# Power.net
KiCad netlist of a schematic drawn in Altium Designer
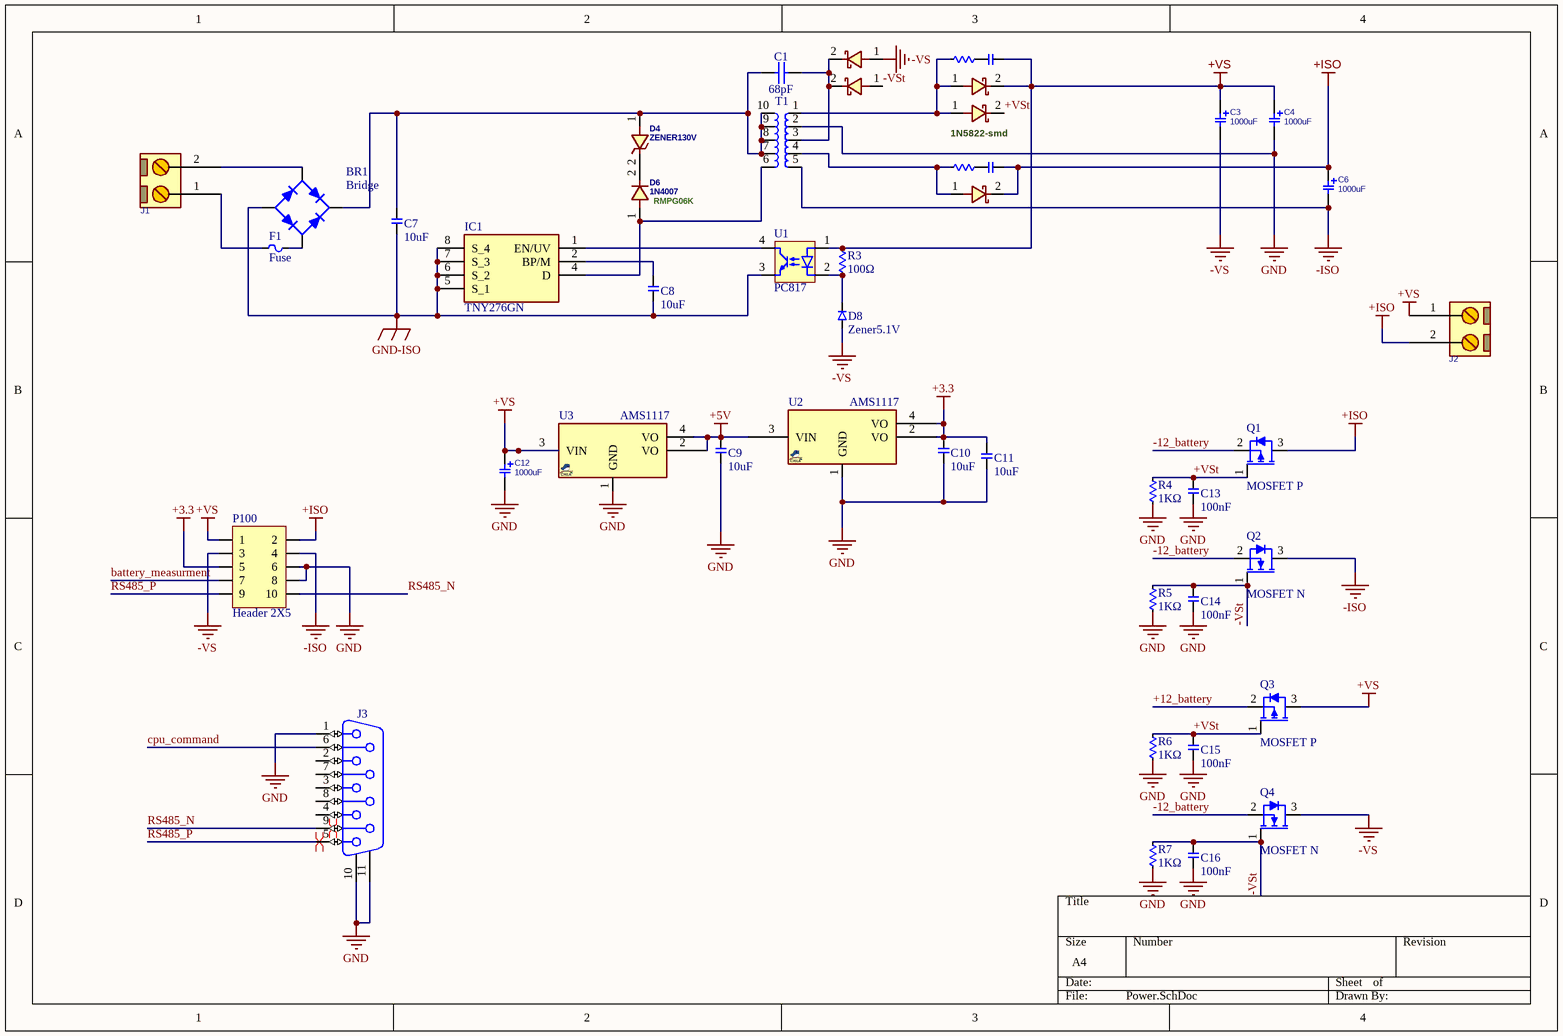
[diagram p0: Power.SchDoc]

(export (version "E")
  (design (tool "Eeschema 10.0.6"))
  (components
    (comp (ref "BR1")
      (value "Bridge")
      (footprint "SOP254P690X270-4L")
      (libsource (lib "Shahnahad") (part "Bridge"))
    )
    (comp (ref "C1")
      (value "68pF")
      (footprint "C_CER_D12")
      (description "Non-polarised capacitor")
      (fields
        (field (name "PART NUMBER") "CCR_68PF_760VAC_10%_VISHAY_VY1")
        (field (name "VOLTAGE") "760VAC")
        (field (name "AUTHOR") "CERN DEM JLC")
      )
      (libsource (lib "Capacitors") (part "Capacitor - non polarized"))
    )
    (comp (ref "C2")
      (value "560pF")
      (footprint "CAP 0603 560p")
      (libsource (lib "Shahnahad") (part "CAP 560pF"))
    )
    (comp (ref "C3")
      (value "1000uF")
      (footprint "C_EL_10X12")
      (description "CAP, THD, ELEC, 10uF, 25V")
      (fields (field (name "MANF") "MANF") (field (name "MANF_P#") "MANF_PART#"))
      (libsource (lib "CapElect_passive") (part "CAP_THD_EL_10u25V"))
    )
    (comp (ref "C4")
      (value "1000uF")
      (footprint "C_EL_10X12")
      (description "CAP, THD, ELEC, 10uF, 25V")
      (fields (field (name "MANF") "MANF") (field (name "MANF_P#") "MANF_PART#"))
      (libsource (lib "CapElect_passive") (part "CAP_THD_EL_10u25V"))
    )
    (comp (ref "C5")
      (value "560pF")
      (footprint "CAP 0603 560p")
      (libsource (lib "Shahnahad") (part "CAP 560pF"))
    )
    (comp (ref "C6")
      (value "1000uF")
      (footprint "C_EL_10X12")
      (description "CAP, THD, ELEC, 10uF, 25V")
      (fields (field (name "MANF") "MANF") (field (name "MANF_P#") "MANF_PART#"))
      (libsource (lib "CapElect_passive") (part "CAP_THD_EL_10u25V"))
    )
    (comp (ref "C7") (value "10uF") (footprint "C_EL_10X12") (libsource (lib "Shahnahad") (part "CAP 10uF")))
    (comp (ref "C8") (value "10uF") (footprint "C_CER_M5") (libsource (lib "Shahnahad") (part "CAP 10uF")))
    (comp (ref "C9")
      (value "10uF")
      (footprint "CAP 0805 10u")
      (libsource (lib "Shahnahad") (part "CAP 10uF"))
    )
    (comp (ref "C10")
      (value "10uF")
      (footprint "CAP 0805 10u")
      (libsource (lib "Shahnahad") (part "CAP 10uF"))
    )
    (comp (ref "C11")
      (value "10uF")
      (footprint "CAP 0805 10u")
      (libsource (lib "Shahnahad") (part "CAP 10uF"))
    )
    (comp (ref "C12")
      (value "1000uF")
      (footprint "C_EL_10X12")
      (description "CAP, THD, ELEC, 10uF, 25V")
      (fields (field (name "MANF") "MANF") (field (name "MANF_P#") "MANF_PART#"))
      (libsource (lib "CapElect_passive") (part "CAP_THD_EL_10u25V"))
    )
    (comp (ref "C13")
      (value "100nF")
      (footprint "CAP 0603 100n")
      (libsource (lib "Shahnahad") (part "CAP 100nF"))
    )
    (comp (ref "C14")
      (value "100nF")
      (footprint "CAP 0603 100n")
      (libsource (lib "Shahnahad") (part "CAP 100nF"))
    )
    (comp (ref "C15")
      (value "100nF")
      (footprint "CAP 0603 100n")
      (libsource (lib "Shahnahad") (part "CAP 100nF"))
    )
    (comp (ref "C16")
      (value "100nF")
      (footprint "CAP 0603 100n")
      (libsource (lib "Shahnahad") (part "CAP 100nF"))
    )
    (comp (ref "D1")
      (value "SS34")
      (footprint "D_SMB")
      (description "DIODE, SCHOTTKY, 20V, 3A")
      (fields (field (name "MANF") "VISHAY"))
      (libsource (lib "diode") (part "DIODE_SMD_SCHOTTKY_SS34"))
    )
    (comp (ref "D2")
      (value "SS34")
      (footprint "d_sod123w")
      (description "DIODE, SCHOTTKY, 20V, 3A")
      (fields (field (name "MANF") "VISHAY"))
      (libsource (lib "diode") (part "DIODE_SMD_SCHOTTKY_SS34"))
    )
    (comp (ref "D3")
      (value "SS34")
      (footprint "D_SMB")
      (description "DIODE, SCHOTTKY, 20V, 3A")
      (fields (field (name "MANF") "VISHAY"))
      (libsource (lib "diode") (part "DIODE_SMD_SCHOTTKY_SS34"))
    )
    (comp (ref "D4")
      (value "ZENER130V")
      (footprint "D_SMB")
      (description "DIODE, ZENER, 1W")
      (fields (field (name "MANF") "Diodes") (field (name "MANF_P#") "ZENER15V"))
      (libsource (lib "diode") (part "DIODE_THD_ZENER_1W"))
    )
    (comp (ref "D5")
      (value "SS34")
      (footprint "D_SOD123W")
      (description "DIODE, SCHOTTKY, 20V, 3A")
      (fields (field (name "MANF") "VISHAY"))
      (libsource (lib "diode") (part "DIODE_SMD_SCHOTTKY_SS34"))
    )
    (comp (ref "D6")
      (value "1N4007")
      (footprint "D_SMB")
      (description "DIODE, GENERAL PURPOSE, 1000V/1A")
      (fields (field (name "MANF") "Diodes"))
      (libsource (lib "diode") (part "DIODE_THD_1N4007"))
    )
    (comp (ref "D7")
      (value "SS34")
      (footprint "D_SMB")
      (description "DIODE, SCHOTTKY, 20V, 3A")
      (fields (field (name "MANF") "VISHAY"))
      (libsource (lib "diode") (part "DIODE_SMD_SCHOTTKY_SS34"))
    )
    (comp (ref "D8")
      (value "Zener5.1V")
      (footprint "DIOMELF3515L")
      (libsource (lib "Shahnahad") (part "Diode"))
    )
    (comp (ref "F1") (value "Fuse") (footprint "Fuse 2410") (libsource (lib "Shahnahad") (part "Fuse")))
    (comp (ref "IC1")
      (value "TNY276GN")
      (footprint "SMD-8C")
      (description "Integrated Circuit")
      (fields (field (name "MOUSER PART NUMBER") "869-TNY276GN") (field (name "RS PART NUMBER") "0533737"))
      (libsource (lib "SamacSys") (part "TNY276GN"))
    )
    (comp (ref "J1")
      (value "CONN_TB2")
      (footprint "TBG_2")
      (description "CONN, TERMINAL BLOCK, 5.08mm pitch")
      (libsource (lib "") (part "CONN_TB2_1"))
    )
    (comp (ref "J2")
      (value "CONN_TB2")
      (footprint "TBG_2")
      (description "CONN, TERMINAL BLOCK, 5.08mm pitch")
      (libsource (lib "Chila") (part "CONN_TB2"))
    )
    (comp (ref "J3")
      (value "D-Sub 9F")
      (footprint "FCI_D09S24A4GV00LF")
      (description "Connector D-sub 9 Female")
      (fields
        (field (name "PART NUMBER") "FCI_D09S24A4GV00LF")
        (field (name "MANUFACTURER") "FCI")
        (field (name "AUTHOR") "CERN DEM JMW")
      )
      (libsource (lib "Connectors") (part "Connector D-sub 9 Female"))
    )
    (comp (ref "P100")
      (value "Header 2X5")
      (footprint "HDR 2X5 F ST 2.54")
      (libsource (lib "Shahnahad") (part "Header 2X5"))
    )
    (comp (ref "Q1") (value "MOSFET P") (footprint "SOT23") (libsource (lib "Shahnahad") (part "MOSFET P")))
    (comp (ref "Q2") (value "MOSFET N") (footprint "SOT23") (libsource (lib "Shahnahad") (part "MOSFET N")))
    (comp (ref "Q3") (value "MOSFET P") (footprint "SOT23") (libsource (lib "Shahnahad") (part "MOSFET P")))
    (comp (ref "Q4") (value "MOSFET N") (footprint "SOT23") (libsource (lib "Shahnahad") (part "MOSFET N")))
    (comp (ref "R1") (value "18Ω") (footprint "RES 0603 18") (libsource (lib "Shahnahad") (part "RES 18")))
    (comp (ref "R2") (value "18Ω") (footprint "RES 0603 18") (libsource (lib "Shahnahad") (part "RES 18")))
    (comp (ref "R3") (value "100Ω") (footprint "RES 0603 100") (libsource (lib "Shahnahad") (part "RES 100")))
    (comp (ref "R4") (value "1KΩ") (footprint "RES 0603 1K") (libsource (lib "Shahnahad") (part "RES 1K")))
    (comp (ref "R5") (value "1KΩ") (footprint "RES 0603 1K") (libsource (lib "Shahnahad") (part "RES 1K")))
    (comp (ref "R6") (value "1KΩ") (footprint "RES 0603 1K") (libsource (lib "Shahnahad") (part "RES 1K")))
    (comp (ref "R7") (value "1KΩ") (footprint "RES 0603 1K") (libsource (lib "Shahnahad") (part "RES 1K")))
    (comp (ref "T1")
      (value "Transformer 5+5")
      (footprint "EE19 5+5")
      (libsource (lib "Shahnahad") (part "Transformer 5+5"))
    )
    (comp (ref "U1") (value "PC817") (footprint "PC817") (libsource (lib "Shahnahad") (part "PC817")))
    (comp (ref "U2")
      (value "AMS1117")
      (footprint "SOT223_4")
      (description "REG, Linear, LDO1V, 0.8A, SOT-223")
      (fields
        (field (name "MANF_P#") "LD1117, LM1117, AMS1117, TLV1117, REG1117, NCP1117, LT1117, SPX1117")
        (field (name "MANF") "TI, ON, ST")
      )
      (libsource (lib "reg_linear_1117") (part "VREG_1117_SOT223"))
    )
    (comp (ref "U3")
      (value "AMS1117")
      (footprint "SOT223_4")
      (description "REG, Linear, LDO1V, 0.8A, SOT-223")
      (fields
        (field (name "MANF_P#") "LD1117, LM1117, AMS1117, TLV1117, REG1117, NCP1117, LT1117, SPX1117")
        (field (name "MANF") "TI, ON, ST")
      )
      (libsource (lib "reg_linear_1117") (part "VREG_1117_SOT223"))
    )
  )
  (nets
    (net (code "1") (name "+3.3") (class "Default")
      (node (ref "C10") (pin "1") (pintype "passive"))
      (node (ref "C11") (pin "1") (pintype "passive"))
      (node (ref "P100") (pin "5") (pinfunction "5_5") (pintype "passive"))
      (node (ref "U2") (pin "2") (pinfunction "VO_2") (pintype "passive"))
      (node (ref "U2") (pin "4") (pinfunction "VO_4") (pintype "passive"))
    )
    (net (code "2") (name "+5V") (class "Default")
      (node (ref "C9") (pin "1") (pintype "passive"))
      (node (ref "U2") (pin "3") (pinfunction "VIN_3") (pintype "passive"))
      (node (ref "U3") (pin "2") (pinfunction "VO_2") (pintype "passive"))
      (node (ref "U3") (pin "4") (pinfunction "VO_4") (pintype "passive"))
    )
    (net (code "3") (name "+ISO") (class "Default")
      (node (ref "C5") (pin "2") (pintype "passive"))
      (node (ref "C6") (pin "1") (pinfunction "1_1") (pintype "passive"))
      (node (ref "D7") (pin "2") (pinfunction "2_2") (pintype "passive"))
      (node (ref "J2") (pin "2") (pinfunction "2_2") (pintype "passive"))
      (node (ref "P100") (pin "2") (pinfunction "2_2") (pintype "passive"))
      (node (ref "Q1") (pin "3") (pinfunction "D_3") (pintype "passive"))
    )
    (net (code "4") (name "+VS") (class "Default")
      (node (ref "C12") (pin "1") (pinfunction "1_1") (pintype "passive"))
      (node (ref "C2") (pin "2") (pintype "passive"))
      (node (ref "C3") (pin "1") (pinfunction "1_1") (pintype "passive"))
      (node (ref "C4") (pin "1") (pinfunction "1_1") (pintype "passive"))
      (node (ref "D3") (pin "2") (pinfunction "2_2") (pintype "passive"))
      (node (ref "J2") (pin "1") (pinfunction "1_1") (pintype "passive"))
      (node (ref "P100") (pin "1") (pinfunction "1_1") (pintype "passive"))
      (node (ref "Q3") (pin "3") (pinfunction "D_3") (pintype "passive"))
      (node (ref "R3") (pin "2") (pintype "passive"))
      (node (ref "U1") (pin "1") (pinfunction "1_1") (pintype "passive"))
      (node (ref "U3") (pin "3") (pinfunction "VIN_3") (pintype "passive"))
    )
    (net (code "5") (name "-ISO") (class "Default")
      (node (ref "C6") (pin "2") (pinfunction "2_2") (pintype "passive"))
      (node (ref "P100") (pin "4") (pinfunction "4_4") (pintype "passive"))
      (node (ref "Q2") (pin "3") (pinfunction "D_3") (pintype "passive"))
      (node (ref "T1") (pin "5") (pintype "passive"))
    )
    (net (code "6") (name "-VS") (class "Default")
      (node (ref "C3") (pin "2") (pinfunction "2_2") (pintype "passive"))
      (node (ref "D1") (pin "1") (pinfunction "1_1") (pintype "passive"))
      (node (ref "D8") (pin "2") (pintype "passive"))
      (node (ref "P100") (pin "3") (pinfunction "3_3") (pintype "passive"))
      (node (ref "Q4") (pin "3") (pinfunction "D_3") (pintype "passive"))
    )
    (net (code "7") (name "/+12_battery") (class "Default")
      (node (ref "Q3") (pin "2") (pinfunction "S_2") (pintype "passive"))
    )
    (net (code "8") (name "/+VSt") (class "Default")
      (node (ref "C13") (pin "1") (pintype "passive"))
      (node (ref "C15") (pin "1") (pintype "passive"))
      (node (ref "D5") (pin "2") (pinfunction "2_2") (pintype "passive"))
      (node (ref "Q1") (pin "1") (pinfunction "G_1") (pintype "passive"))
      (node (ref "Q3") (pin "1") (pinfunction "G_1") (pintype "passive"))
      (node (ref "R4") (pin "1") (pintype "passive"))
      (node (ref "R6") (pin "1") (pintype "passive"))
    )
    (net (code "9") (name "/-12_battery") (class "Default")
      (node (ref "Q1") (pin "2") (pinfunction "S_2") (pintype "passive"))
      (node (ref "Q2") (pin "2") (pinfunction "S_2") (pintype "passive"))
      (node (ref "Q4") (pin "2") (pinfunction "S_2") (pintype "passive"))
    )
    (net (code "10") (name "/-VSt") (class "Default")
      (node (ref "C14") (pin "1") (pintype "passive"))
      (node (ref "C16") (pin "1") (pintype "passive"))
      (node (ref "D2") (pin "1") (pinfunction "1_1") (pintype "passive"))
      (node (ref "Q2") (pin "1") (pinfunction "G_1") (pintype "passive"))
      (node (ref "Q4") (pin "1") (pinfunction "G_1") (pintype "passive"))
      (node (ref "R5") (pin "1") (pintype "passive"))
      (node (ref "R7") (pin "1") (pintype "passive"))
    )
    (net (code "11") (name "/RS485_N") (class "Default")
      (node (ref "J3") (pin "9") (pinfunction "9_9") (pintype "bidirectional"))
      (node (ref "P100") (pin "10") (pinfunction "10_10") (pintype "passive"))
    )
    (net (code "12") (name "/RS485_P") (class "Default")
      (node (ref "J3") (pin "5") (pinfunction "5_5") (pintype "bidirectional"))
      (node (ref "P100") (pin "9") (pinfunction "9_9") (pintype "passive"))
    )
    (net (code "13") (name "/battery_measurment") (class "Default")
      (node (ref "P100") (pin "7") (pinfunction "7_7") (pintype "passive"))
    )
    (net (code "14") (name "/cpu_command") (class "Default")
      (node (ref "J3") (pin "6") (pinfunction "6_6") (pintype "bidirectional"))
    )
    (net (code "15") (name "GND") (class "Default")
      (node (ref "C10") (pin "2") (pintype "passive"))
      (node (ref "C11") (pin "2") (pintype "passive"))
      (node (ref "C12") (pin "2") (pinfunction "2_2") (pintype "passive"))
      (node (ref "C13") (pin "2") (pintype "passive"))
      (node (ref "C14") (pin "2") (pintype "passive"))
      (node (ref "C15") (pin "2") (pintype "passive"))
      (node (ref "C16") (pin "2") (pintype "passive"))
      (node (ref "C4") (pin "2") (pinfunction "2_2") (pintype "passive"))
      (node (ref "C9") (pin "2") (pintype "passive"))
      (node (ref "J3") (pin "1") (pinfunction "1_1") (pintype "bidirectional"))
      (node (ref "J3") (pin "10") (pinfunction "10_10") (pintype "passive"))
      (node (ref "J3") (pin "11") (pinfunction "11_11") (pintype "passive"))
      (node (ref "P100") (pin "6") (pinfunction "6_6") (pintype "passive"))
      (node (ref "P100") (pin "8") (pinfunction "8_8") (pintype "passive"))
      (node (ref "R4") (pin "2") (pintype "passive"))
      (node (ref "R5") (pin "2") (pintype "passive"))
      (node (ref "R6") (pin "2") (pintype "passive"))
      (node (ref "R7") (pin "2") (pintype "passive"))
      (node (ref "T1") (pin "2") (pintype "passive"))
      (node (ref "U2") (pin "1") (pinfunction "GND_1") (pintype "passive"))
      (node (ref "U3") (pin "1") (pinfunction "GND_1") (pintype "passive"))
    )
    (net (code "16") (name "GND-ISO") (class "Default")
      (node (ref "BR1") (pin "2") (pinfunction "-_2") (pintype "passive"))
      (node (ref "C7") (pin "2") (pintype "passive"))
      (node (ref "C8") (pin "2") (pintype "passive"))
      (node (ref "IC1") (pin "5") (pinfunction "S_1_5") (pintype "passive"))
      (node (ref "IC1") (pin "6") (pinfunction "S_2_6") (pintype "passive"))
      (node (ref "IC1") (pin "7") (pinfunction "S_3_7") (pintype "passive"))
      (node (ref "IC1") (pin "8") (pinfunction "S_4_8") (pintype "passive"))
      (node (ref "U1") (pin "3") (pinfunction "3_3") (pintype "passive"))
    )
    (net (code "17") (name "Net-(BR1-+)") (class "Default")
      (node (ref "BR1") (pin "1") (pinfunction "+_1") (pintype "passive"))
      (node (ref "C1") (pin "1") (pinfunction "1_1") (pintype "passive"))
      (node (ref "C7") (pin "1") (pintype "passive"))
      (node (ref "D4") (pin "1") (pinfunction "1_1") (pintype "passive"))
      (node (ref "T1") (pin "10") (pintype "passive"))
      (node (ref "T1") (pin "7") (pintype "passive"))
      (node (ref "T1") (pin "8") (pintype "passive"))
      (node (ref "T1") (pin "9") (pintype "passive"))
    )
    (net (code "18") (name "Net-(BR1-~-Pad3)") (class "Default")
      (node (ref "BR1") (pin "3") (pinfunction "~_3") (pintype "passive"))
      (node (ref "F1") (pin "2") (pintype "passive"))
    )
    (net (code "19") (name "Net-(BR1-~-Pad4)") (class "Default")
      (node (ref "BR1") (pin "4") (pinfunction "~_4") (pintype "passive"))
      (node (ref "J1") (pin "2") (pinfunction "2_2") (pintype "passive"))
    )
    (net (code "20") (name "Net-(C1-Pad2)") (class "Default")
      (node (ref "C1") (pin "2") (pinfunction "2_2") (pintype "passive"))
      (node (ref "D1") (pin "2") (pinfunction "2_2") (pintype "passive"))
      (node (ref "D2") (pin "2") (pinfunction "2_2") (pintype "passive"))
      (node (ref "T1") (pin "3") (pintype "passive"))
    )
    (net (code "21") (name "Net-(C2-Pad1)") (class "Default")
      (node (ref "C2") (pin "1") (pintype "passive"))
      (node (ref "R1") (pin "2") (pintype "passive"))
    )
    (net (code "22") (name "Net-(C5-Pad1)") (class "Default")
      (node (ref "C5") (pin "1") (pintype "passive"))
      (node (ref "R2") (pin "2") (pintype "passive"))
    )
    (net (code "23") (name "Net-(D3-Pad1)") (class "Default")
      (node (ref "D3") (pin "1") (pinfunction "1_1") (pintype "passive"))
      (node (ref "D5") (pin "1") (pinfunction "1_1") (pintype "passive"))
      (node (ref "R1") (pin "1") (pintype "passive"))
      (node (ref "T1") (pin "1") (pintype "passive"))
    )
    (net (code "24") (name "Net-(D4-Pad2)") (class "Default")
      (node (ref "D4") (pin "2") (pinfunction "2_2") (pintype "passive"))
      (node (ref "D6") (pin "2") (pinfunction "2_2") (pintype "passive"))
    )
    (net (code "25") (name "Net-(D7-Pad1)") (class "Default")
      (node (ref "D7") (pin "1") (pinfunction "1_1") (pintype "passive"))
      (node (ref "R2") (pin "1") (pintype "passive"))
      (node (ref "T1") (pin "4") (pintype "passive"))
    )
    (net (code "26") (name "Net-(D8-Pad1)") (class "Default")
      (node (ref "D8") (pin "1") (pintype "passive"))
      (node (ref "R3") (pin "1") (pintype "passive"))
      (node (ref "U1") (pin "2") (pinfunction "2_2") (pintype "passive"))
    )
    (net (code "27") (name "Net-(F1-Pad1)") (class "Default")
      (node (ref "F1") (pin "1") (pintype "passive"))
      (node (ref "J1") (pin "1") (pinfunction "1_1") (pintype "passive"))
    )
    (net (code "28") (name "Net-(IC1-BP{slash}M)") (class "Default")
      (node (ref "C8") (pin "1") (pintype "passive"))
      (node (ref "IC1") (pin "2") (pinfunction "BP/M_2") (pintype "passive"))
    )
    (net (code "29") (name "Net-(IC1-D)") (class "Default")
      (node (ref "D6") (pin "1") (pinfunction "1_1") (pintype "passive"))
      (node (ref "IC1") (pin "4") (pinfunction "D_4") (pintype "passive"))
      (node (ref "T1") (pin "6") (pintype "passive"))
    )
    (net (code "30") (name "Net-(IC1-EN{slash}UV)") (class "Default")
      (node (ref "IC1") (pin "1") (pinfunction "EN/UV_1") (pintype "passive"))
      (node (ref "U1") (pin "4") (pinfunction "4_4") (pintype "passive"))
    )
    (net (code "31") (name "unconnected-(J3-Pad2)") (class "Default")
      (node (ref "J3") (pin "2") (pinfunction "2_2") (pintype "bidirectional"))
    )
    (net (code "32") (name "unconnected-(J3-Pad3)") (class "Default")
      (node (ref "J3") (pin "3") (pinfunction "3_3") (pintype "bidirectional"))
    )
    (net (code "33") (name "unconnected-(J3-Pad4)") (class "Default")
      (node (ref "J3") (pin "4") (pinfunction "4_4") (pintype "bidirectional"))
    )
    (net (code "34") (name "unconnected-(J3-Pad7)") (class "Default")
      (node (ref "J3") (pin "7") (pinfunction "7_7") (pintype "bidirectional"))
    )
    (net (code "35") (name "unconnected-(J3-Pad8)") (class "Default")
      (node (ref "J3") (pin "8") (pinfunction "8_8") (pintype "bidirectional"))
    )
  )
)
